# LFO_V01.net
KiCad netlist of a schematic drawn in EAGLE
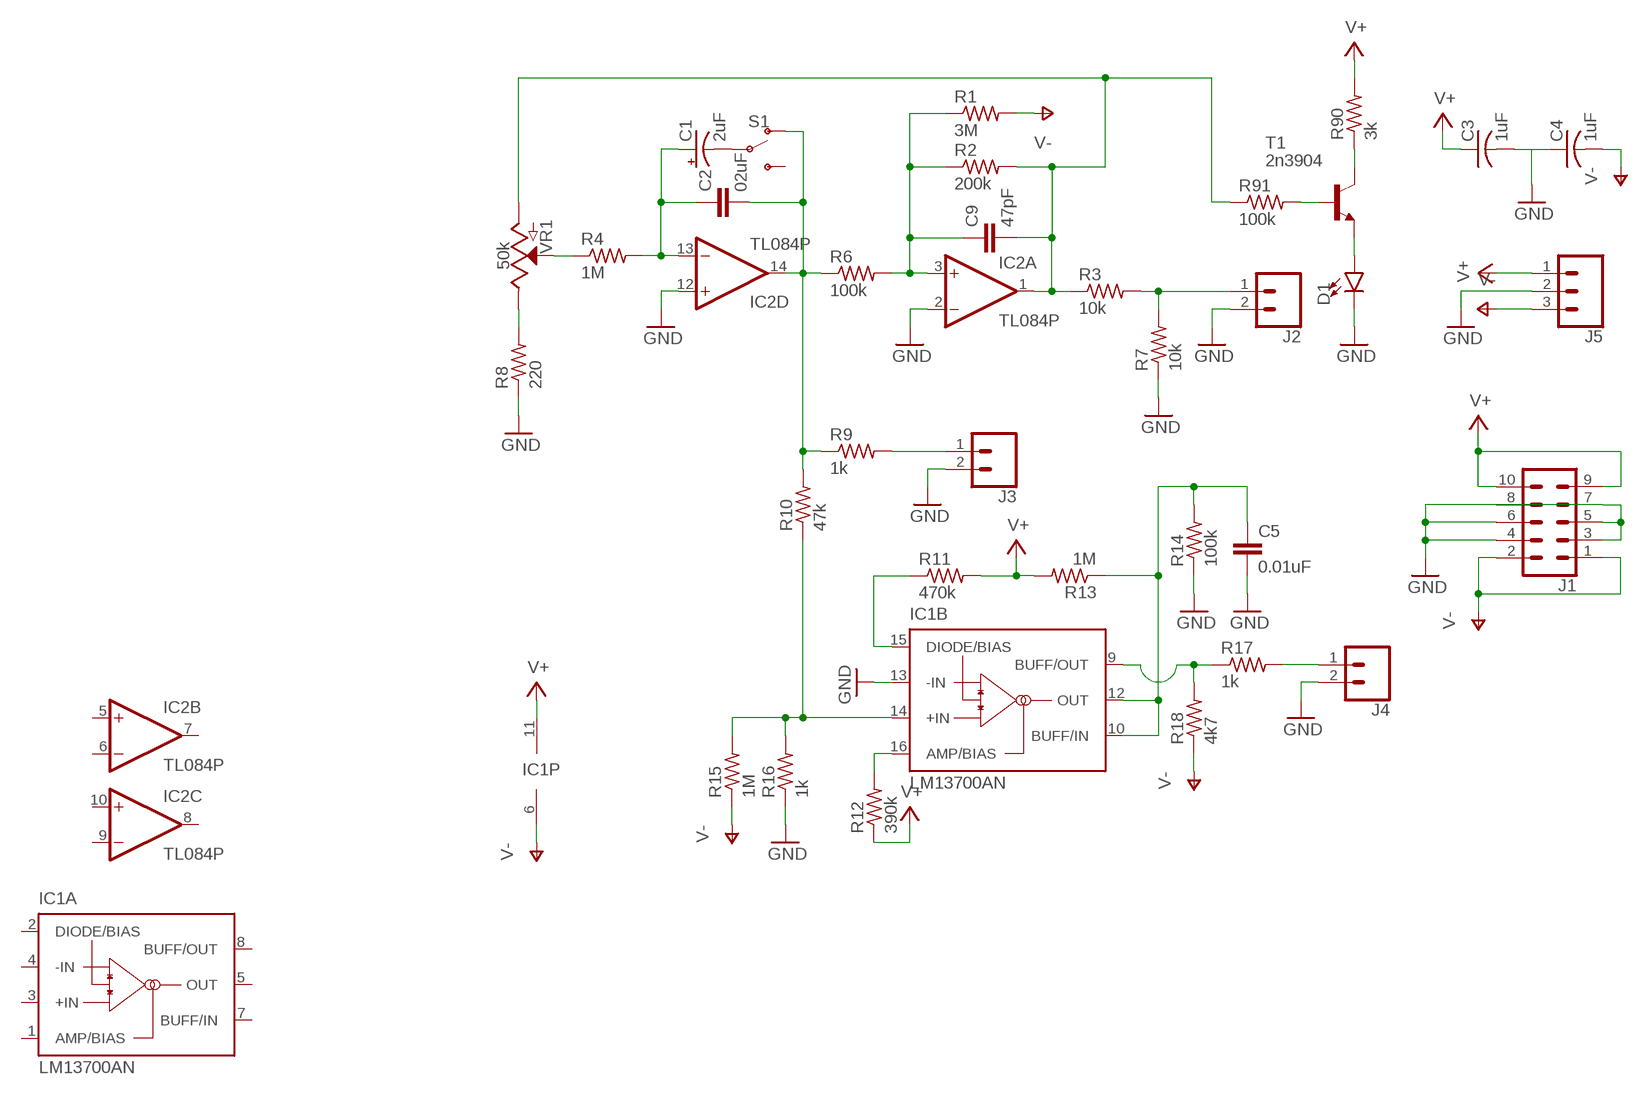
[diagram p0: schematic, sheet 1]

(export (version "E")
  (design (tool "Eeschema 10.0.6"))
  (components
    (comp (ref "C1")
      (value "2uF")
      (footprint "eagle-import:E3,5-8")
      (libsource (lib "eagle-import") (part "CPOL-USE3.5-8"))
    )
    (comp (ref "C2")
      (value "02uF")
      (footprint "eagle-import:C050-025X075")
      (libsource (lib "eagle-import") (part "resistor_348_C-EU050-025X075"))
    )
    (comp (ref "C3")
      (value "1uF")
      (footprint "eagle-import:C102-043X133")
      (libsource (lib "eagle-import") (part "C-US102-043X133"))
    )
    (comp (ref "C4")
      (value "1uF")
      (footprint "eagle-import:C102-043X133")
      (libsource (lib "eagle-import") (part "C-US102-043X133"))
    )
    (comp (ref "C5")
      (value "0.01uF")
      (footprint "eagle-import:C050-024X044")
      (libsource (lib "eagle-import") (part "C-EU050-024X044"))
    )
    (comp (ref "C9")
      (value "47pF")
      (footprint "eagle-import:C050-025X075")
      (libsource (lib "eagle-import") (part "resistor_348_C-EU050-025X075"))
    )
    (comp (ref "D1")
      (value "LED5MM-KIT")
      (footprint "eagle-import:LED_5MM-KIT")
      (libsource (lib "eagle-import") (part "LED5MM-KIT"))
    )
    (comp (ref "IC1")
      (value "LM13700AN")
      (footprint "eagle-import:DIL16")
      (libsource (lib "eagle-import") (part "LM13600NA"))
    )
    (comp (ref "IC2")
      (value "TL084P")
      (footprint "eagle-import:DIL14")
      (libsource (lib "eagle-import") (part "TL084P"))
    )
    (comp (ref "J1")
      (value "CONN_05X2SHD")
      (footprint "eagle-import:2X5-SHROUDED")
      (libsource (lib "eagle-import") (part "CONN_05X2SHD"))
    )
    (comp (ref "J2")
      (value "CONN_023.5MM-NO_SILK")
      (footprint "eagle-import:SCREWTERMINAL-3.5MM-2-NS")
      (libsource (lib "eagle-import") (part "CONN_023.5MM-NO_SILK"))
    )
    (comp (ref "J3")
      (value "CONN_023.5MM-NO_SILK")
      (footprint "eagle-import:SCREWTERMINAL-3.5MM-2-NS")
      (libsource (lib "eagle-import") (part "CONN_023.5MM-NO_SILK"))
    )
    (comp (ref "J4")
      (value "CONN_023.5MM-NO_SILK")
      (footprint "eagle-import:SCREWTERMINAL-3.5MM-2-NS")
      (libsource (lib "eagle-import") (part "CONN_023.5MM-NO_SILK"))
    )
    (comp (ref "J5")
      (value "CONN_03-SCREW-5MM")
      (footprint "eagle-import:SCREWTERMINAL-5MM-3")
      (libsource (lib "eagle-import") (part "CONN_03-SCREW-5MM"))
    )
    (comp (ref "R1")
      (value "3M")
      (footprint "eagle-import:0204_7")
      (libsource (lib "eagle-import") (part "R-US_0204/7"))
    )
    (comp (ref "R2")
      (value "200k")
      (footprint "eagle-import:0204_7")
      (libsource (lib "eagle-import") (part "R-US_0204/7"))
    )
    (comp (ref "R3")
      (value "10k")
      (footprint "eagle-import:0204_7")
      (libsource (lib "eagle-import") (part "R-US_0204/7"))
    )
    (comp (ref "R4")
      (value "1M")
      (footprint "eagle-import:0204_7")
      (libsource (lib "eagle-import") (part "R-US_0204/7"))
    )
    (comp (ref "R6")
      (value "100k")
      (footprint "eagle-import:0204_7")
      (libsource (lib "eagle-import") (part "R-US_0204/7"))
    )
    (comp (ref "R7")
      (value "10k")
      (footprint "eagle-import:0204_7")
      (libsource (lib "eagle-import") (part "R-US_0204/7"))
    )
    (comp (ref "R8")
      (value "220")
      (footprint "eagle-import:0204_7")
      (libsource (lib "eagle-import") (part "R-US_0204/7"))
    )
    (comp (ref "R9")
      (value "1k")
      (footprint "eagle-import:0204_7")
      (libsource (lib "eagle-import") (part "R-US_0204/7"))
    )
    (comp (ref "R10")
      (value "47k")
      (footprint "eagle-import:0204_7")
      (libsource (lib "eagle-import") (part "R-US_0204/7"))
    )
    (comp (ref "R11")
      (value "470k")
      (footprint "eagle-import:0204_7")
      (libsource (lib "eagle-import") (part "R-US_0204/7"))
    )
    (comp (ref "R12")
      (value "390k")
      (footprint "eagle-import:0204_7")
      (libsource (lib "eagle-import") (part "R-US_0204/7"))
    )
    (comp (ref "R13")
      (value "1M")
      (footprint "eagle-import:0204_7")
      (libsource (lib "eagle-import") (part "R-US_0204/7"))
    )
    (comp (ref "R14")
      (value "100k")
      (footprint "eagle-import:0204_7")
      (libsource (lib "eagle-import") (part "R-US_0204/7"))
    )
    (comp (ref "R15")
      (value "1M")
      (footprint "eagle-import:0204_7")
      (libsource (lib "eagle-import") (part "R-US_0204/7"))
    )
    (comp (ref "R16")
      (value "1k")
      (footprint "eagle-import:0204_7")
      (libsource (lib "eagle-import") (part "R-US_0204/7"))
    )
    (comp (ref "R17")
      (value "1k")
      (footprint "eagle-import:0204_7")
      (libsource (lib "eagle-import") (part "R-US_0204/7"))
    )
    (comp (ref "R18")
      (value "4k7")
      (footprint "eagle-import:0204_7")
      (libsource (lib "eagle-import") (part "R-US_0204/7"))
    )
    (comp (ref "R90")
      (value "3k")
      (footprint "eagle-import:0204_7")
      (libsource (lib "eagle-import") (part "R-US_0204/7"))
    )
    (comp (ref "R91")
      (value "100k")
      (footprint "eagle-import:0204_7")
      (libsource (lib "eagle-import") (part "R-US_0204/7"))
    )
    (comp (ref "S1")
      (value "SWITCH-SPDT-PTH-11.6X4.0MM")
      (footprint "eagle-import:SWITCH_SPDT_PTH_11.6X4.0MM")
      (libsource (lib "eagle-import") (part "SWITCH-SPDT-PTH-11.6X4.0MM"))
    )
    (comp (ref "T1")
      (value "2n3904")
      (footprint "eagle-import:TO92-EBC")
      (libsource (lib "eagle-import") (part "-NPN-TO92-EBC"))
    )
    (comp (ref "VR1")
      (value "50k")
      (footprint "eagle-import:POT-PTH-ALPS-KIT")
      (libsource (lib "eagle-import") (part "POTENTIOMETER-PTH-9MM-1/20W-20%-KIT"))
    )
  )
  (nets
    (net (code "1") (name "GND") (class "Default")
      (node (ref "C3") (pin "2") (pinfunction "2_2") (pintype "passive"))
      (node (ref "C4") (pin "1") (pinfunction "1_1") (pintype "passive"))
      (node (ref "C5") (pin "2") (pinfunction "2_2") (pintype "passive"))
      (node (ref "D1") (pin "K") (pinfunction "C_K") (pintype "passive"))
      (node (ref "IC1") (pin "13") (pinfunction "-IN_13") (pintype "input"))
      (node (ref "IC2") (pin "12") (pinfunction "+IN_12") (pintype "input"))
      (node (ref "IC2") (pin "2") (pinfunction "-IN_2") (pintype "input"))
      (node (ref "J1") (pin "3") (pinfunction "3_3") (pintype "passive"))
      (node (ref "J1") (pin "4") (pinfunction "4_4") (pintype "passive"))
      (node (ref "J1") (pin "5") (pinfunction "5_5") (pintype "passive"))
      (node (ref "J1") (pin "6") (pinfunction "6_6") (pintype "passive"))
      (node (ref "J1") (pin "7") (pinfunction "7_7") (pintype "passive"))
      (node (ref "J1") (pin "8") (pinfunction "8_8") (pintype "passive"))
      (node (ref "J2") (pin "2") (pinfunction "2_2") (pintype "passive"))
      (node (ref "J3") (pin "2") (pinfunction "2_2") (pintype "passive"))
      (node (ref "J4") (pin "2") (pinfunction "2_2") (pintype "passive"))
      (node (ref "J5") (pin "2") (pinfunction "2_2") (pintype "passive"))
      (node (ref "R14") (pin "1") (pinfunction "1_1") (pintype "passive"))
      (node (ref "R16") (pin "1") (pinfunction "1_1") (pintype "passive"))
      (node (ref "R7") (pin "1") (pinfunction "1_1") (pintype "passive"))
      (node (ref "R8") (pin "1") (pinfunction "1_1") (pintype "passive"))
    )
    (net (code "2") (name "Net-(D1-PadA)") (class "Default")
      (node (ref "D1") (pin "A") (pinfunction "A_A") (pintype "passive"))
      (node (ref "T1") (pin "E") (pinfunction "E_E") (pintype "passive"))
    )
    (net (code "3") (name "Net-(IC1B-+IN)") (class "Default")
      (node (ref "IC1") (pin "14") (pinfunction "+IN_14") (pintype "input"))
      (node (ref "R10") (pin "1") (pinfunction "1_1") (pintype "passive"))
      (node (ref "R15") (pin "2") (pinfunction "2_2") (pintype "passive"))
      (node (ref "R16") (pin "2") (pinfunction "2_2") (pintype "passive"))
    )
    (net (code "4") (name "Net-(IC1B-AMP{slash}BIAS)") (class "Default")
      (node (ref "IC1") (pin "16") (pinfunction "AMP/BIAS_16") (pintype "passive"))
      (node (ref "R12") (pin "2") (pinfunction "2_2") (pintype "passive"))
    )
    (net (code "5") (name "Net-(IC1B-BUFF{slash}IN)") (class "Default")
      (node (ref "C5") (pin "1") (pinfunction "1_1") (pintype "passive"))
      (node (ref "IC1") (pin "10") (pinfunction "BUFF/IN_10") (pintype "input"))
      (node (ref "IC1") (pin "12") (pinfunction "OUT_12") (pintype "output"))
      (node (ref "R13") (pin "1") (pinfunction "1_1") (pintype "passive"))
      (node (ref "R14") (pin "2") (pinfunction "2_2") (pintype "passive"))
    )
    (net (code "6") (name "Net-(IC1B-BUFF{slash}OUT)") (class "Default")
      (node (ref "IC1") (pin "9") (pinfunction "BUFF/OUT_9") (pintype "output"))
      (node (ref "R17") (pin "1") (pinfunction "1_1") (pintype "passive"))
      (node (ref "R18") (pin "2") (pinfunction "2_2") (pintype "passive"))
    )
    (net (code "7") (name "Net-(IC1B-DIODE{slash}BIAS)") (class "Default")
      (node (ref "IC1") (pin "15") (pinfunction "DIODE/BIAS_15") (pintype "passive"))
      (node (ref "R11") (pin "1") (pinfunction "1_1") (pintype "passive"))
    )
    (net (code "8") (name "Net-(IC2A-+IN)") (class "Default")
      (node (ref "C9") (pin "1") (pinfunction "1_1") (pintype "passive"))
      (node (ref "IC2") (pin "3") (pinfunction "+IN_3") (pintype "input"))
      (node (ref "R1") (pin "1") (pinfunction "1_1") (pintype "passive"))
      (node (ref "R2") (pin "1") (pinfunction "1_1") (pintype "passive"))
      (node (ref "R6") (pin "2") (pinfunction "2_2") (pintype "passive"))
    )
    (net (code "9") (name "Net-(IC2A-OUT)") (class "Default")
      (node (ref "C9") (pin "2") (pinfunction "2_2") (pintype "passive"))
      (node (ref "IC2") (pin "1") (pinfunction "OUT_1") (pintype "output"))
      (node (ref "R2") (pin "2") (pinfunction "2_2") (pintype "passive"))
      (node (ref "R3") (pin "1") (pinfunction "1_1") (pintype "passive"))
      (node (ref "R91") (pin "1") (pinfunction "1_1") (pintype "passive"))
      (node (ref "VR1") (pin "P$3") (pinfunction "A_P$3") (pintype "passive"))
    )
    (net (code "10") (name "Net-(IC2D--IN)") (class "Default")
      (node (ref "C1") (pin "+") (pinfunction "+_+") (pintype "passive"))
      (node (ref "C2") (pin "1") (pinfunction "1_1") (pintype "passive"))
      (node (ref "IC2") (pin "13") (pinfunction "-IN_13") (pintype "input"))
      (node (ref "R4") (pin "2") (pinfunction "2_2") (pintype "passive"))
    )
    (net (code "11") (name "Net-(IC2D-OUT)") (class "Default")
      (node (ref "C2") (pin "2") (pinfunction "2_2") (pintype "passive"))
      (node (ref "IC2") (pin "14") (pinfunction "OUT_14") (pintype "output"))
      (node (ref "R10") (pin "2") (pinfunction "2_2") (pintype "passive"))
      (node (ref "R6") (pin "1") (pinfunction "1_1") (pintype "passive"))
      (node (ref "R9") (pin "1") (pinfunction "1_1") (pintype "passive"))
      (node (ref "S1") (pin "1") (pinfunction "O_1") (pintype "passive"))
    )
    (net (code "12") (name "Net-(J2-Pad1)") (class "Default")
      (node (ref "J2") (pin "1") (pinfunction "1_1") (pintype "passive"))
      (node (ref "R3") (pin "2") (pinfunction "2_2") (pintype "passive"))
      (node (ref "R7") (pin "2") (pinfunction "2_2") (pintype "passive"))
    )
    (net (code "13") (name "Net-(J3-Pad1)") (class "Default")
      (node (ref "J3") (pin "1") (pinfunction "1_1") (pintype "passive"))
      (node (ref "R9") (pin "2") (pinfunction "2_2") (pintype "passive"))
    )
    (net (code "14") (name "Net-(J4-Pad1)") (class "Default")
      (node (ref "J4") (pin "1") (pinfunction "1_1") (pintype "passive"))
      (node (ref "R17") (pin "2") (pinfunction "2_2") (pintype "passive"))
    )
    (net (code "15") (name "Net-(R90-Pad1)") (class "Default")
      (node (ref "R90") (pin "1") (pinfunction "1_1") (pintype "passive"))
      (node (ref "T1") (pin "C") (pinfunction "C_C") (pintype "passive"))
    )
    (net (code "16") (name "Net-(R91-Pad2)") (class "Default")
      (node (ref "R91") (pin "2") (pinfunction "2_2") (pintype "passive"))
      (node (ref "T1") (pin "B") (pinfunction "B_B") (pintype "passive"))
    )
    (net (code "17") (name "Net-(S1-P)") (class "Default")
      (node (ref "C1") (pin "-") (pinfunction "-_-") (pintype "passive"))
      (node (ref "S1") (pin "2") (pinfunction "P_2") (pintype "passive"))
    )
    (net (code "18") (name "Net-(VR1-E)") (class "Default")
      (node (ref "R8") (pin "2") (pinfunction "2_2") (pintype "passive"))
      (node (ref "VR1") (pin "P$1") (pinfunction "E_P$1") (pintype "passive"))
    )
    (net (code "19") (name "Net-(VR1-S)") (class "Default")
      (node (ref "R4") (pin "1") (pinfunction "1_1") (pintype "passive"))
      (node (ref "VR1") (pin "P$2") (pinfunction "S_P$2") (pintype "passive"))
    )
    (net (code "20") (name "V+") (class "Default")
      (node (ref "C3") (pin "1") (pinfunction "1_1") (pintype "passive"))
      (node (ref "IC1") (pin "11") (pinfunction "V+_11") (pintype "power_in"))
      (node (ref "J1") (pin "10") (pinfunction "10_10") (pintype "passive"))
      (node (ref "J1") (pin "9") (pinfunction "9_9") (pintype "passive"))
      (node (ref "J5") (pin "1") (pinfunction "1_1") (pintype "passive"))
      (node (ref "R11") (pin "2") (pinfunction "2_2") (pintype "passive"))
      (node (ref "R12") (pin "1") (pinfunction "1_1") (pintype "passive"))
      (node (ref "R13") (pin "2") (pinfunction "2_2") (pintype "passive"))
      (node (ref "R90") (pin "2") (pinfunction "2_2") (pintype "passive"))
    )
    (net (code "21") (name "V-") (class "Default")
      (node (ref "C4") (pin "2") (pinfunction "2_2") (pintype "passive"))
      (node (ref "IC1") (pin "6") (pinfunction "V-_6") (pintype "power_in"))
      (node (ref "J1") (pin "1") (pinfunction "1_1") (pintype "passive"))
      (node (ref "J1") (pin "2") (pinfunction "2_2") (pintype "passive"))
      (node (ref "J5") (pin "3") (pinfunction "3_3") (pintype "passive"))
      (node (ref "R1") (pin "2") (pinfunction "2_2") (pintype "passive"))
      (node (ref "R15") (pin "1") (pinfunction "1_1") (pintype "passive"))
      (node (ref "R18") (pin "1") (pinfunction "1_1") (pintype "passive"))
    )
    (net (code "22") (name "unconnected-(IC1A-+IN-Pad3)") (class "Default")
      (node (ref "IC1") (pin "3") (pinfunction "+IN_3") (pintype "input"))
    )
    (net (code "23") (name "unconnected-(IC1A--IN-Pad4)") (class "Default")
      (node (ref "IC1") (pin "4") (pinfunction "-IN_4") (pintype "input"))
    )
    (net (code "24") (name "unconnected-(IC1A-AMP{slash}BIAS-Pad1)") (class "Default")
      (node (ref "IC1") (pin "1") (pinfunction "AMP/BIAS_1") (pintype "passive"))
    )
    (net (code "25") (name "unconnected-(IC1A-BUFF{slash}IN-Pad7)") (class "Default")
      (node (ref "IC1") (pin "7") (pinfunction "BUFF/IN_7") (pintype "input"))
    )
    (net (code "26") (name "unconnected-(IC1A-BUFF{slash}OUT-Pad8)") (class "Default")
      (node (ref "IC1") (pin "8") (pinfunction "BUFF/OUT_8") (pintype "output"))
    )
    (net (code "27") (name "unconnected-(IC1A-DIODE{slash}BIAS-Pad2)") (class "Default")
      (node (ref "IC1") (pin "2") (pinfunction "DIODE/BIAS_2") (pintype "passive"))
    )
    (net (code "28") (name "unconnected-(IC1A-OUT-Pad5)") (class "Default")
      (node (ref "IC1") (pin "5") (pinfunction "OUT_5") (pintype "output"))
    )
    (net (code "29") (name "unconnected-(IC2B-+IN-Pad5)") (class "Default")
      (node (ref "IC2") (pin "5") (pinfunction "+IN_5") (pintype "input"))
    )
    (net (code "30") (name "unconnected-(IC2B--IN-Pad6)") (class "Default")
      (node (ref "IC2") (pin "6") (pinfunction "-IN_6") (pintype "input"))
    )
    (net (code "31") (name "unconnected-(IC2B-OUT-Pad7)") (class "Default")
      (node (ref "IC2") (pin "7") (pinfunction "OUT_7") (pintype "output"))
    )
    (net (code "32") (name "unconnected-(IC2C-+IN-Pad10)") (class "Default")
      (node (ref "IC2") (pin "10") (pinfunction "+IN_10") (pintype "input"))
    )
    (net (code "33") (name "unconnected-(IC2C--IN-Pad9)") (class "Default")
      (node (ref "IC2") (pin "9") (pinfunction "-IN_9") (pintype "input"))
    )
    (net (code "34") (name "unconnected-(IC2C-OUT-Pad8)") (class "Default")
      (node (ref "IC2") (pin "8") (pinfunction "OUT_8") (pintype "output"))
    )
    (net (code "35") (name "unconnected-(S1-S-Pad3)") (class "Default")
      (node (ref "S1") (pin "3") (pinfunction "S_3") (pintype "passive"))
    )
  )
)
